# power-sch.net
KiCad netlist of a schematic drawn in Altium Designer
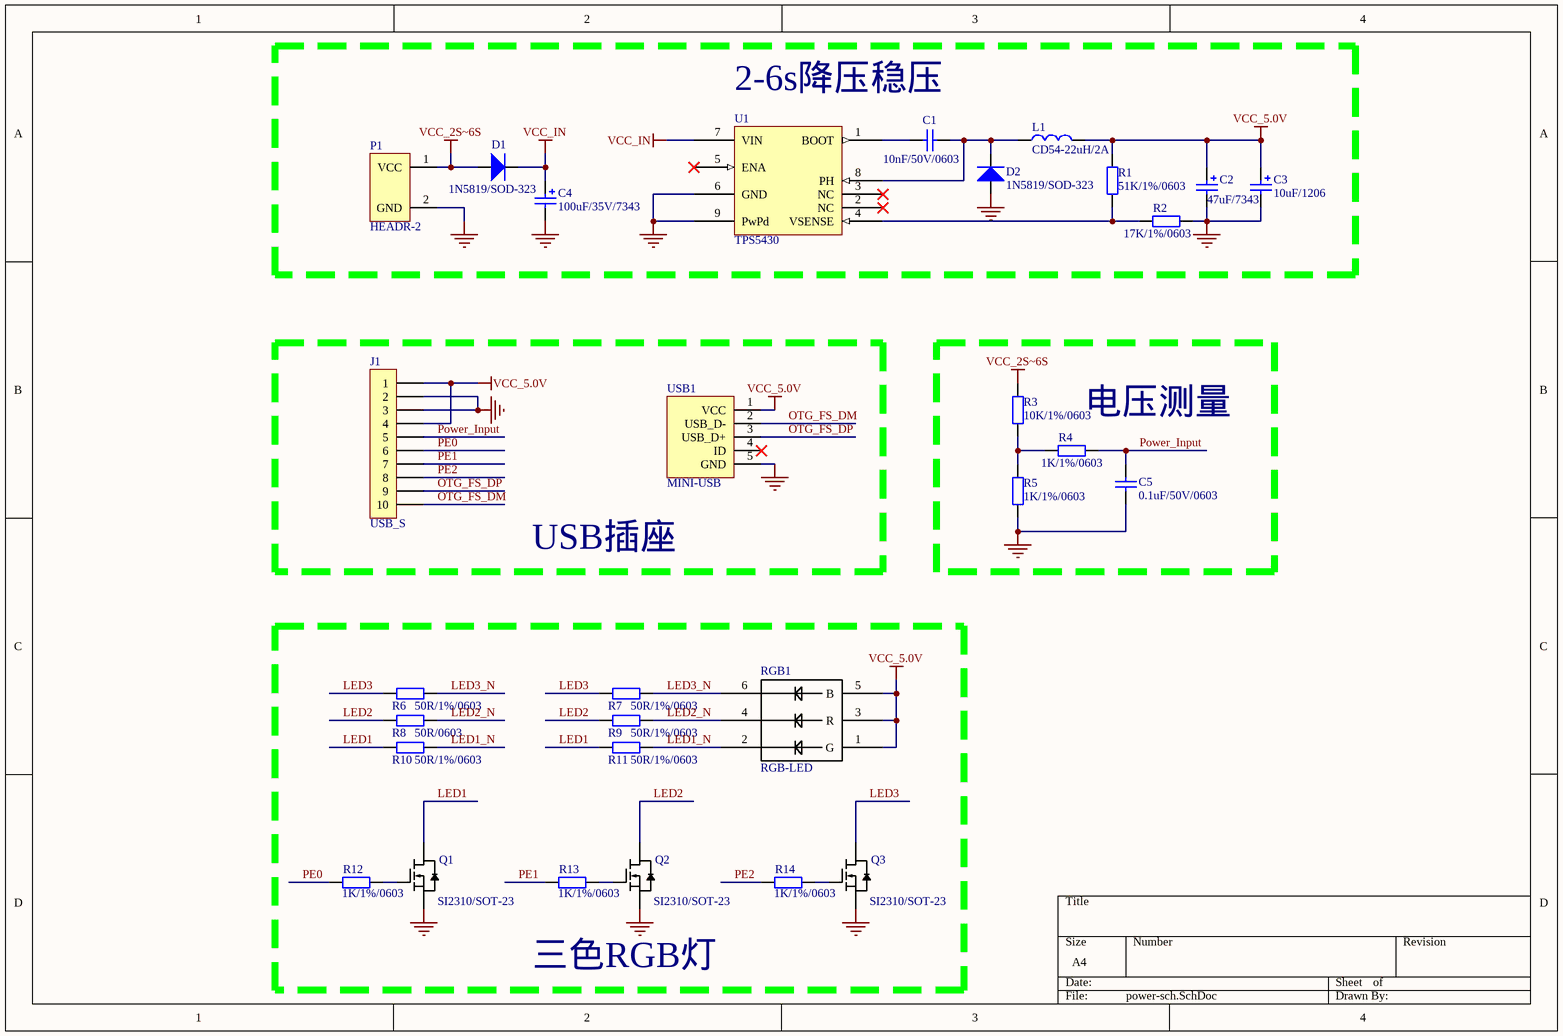
[diagram p0: power-sch.SchDoc]

(export (version "E")
  (design (tool "Eeschema 10.0.6"))
  (components
    (comp (ref "C1")
      (value "10nF/50V/0603")
      (footprint "LC-0603_C")
      (description "Capacitor")
      (fields (field (name "PUBLISHER") "Altium Limited"))
      (libsource (lib "Miscellaneous Devices") (part "Cap"))
    )
    (comp (ref "C2")
      (value "47uF/7343")
      (footprint "LC-CASE-D_7343")
      (description "Polarized Capacitor (Axial)")
      (fields (field (name "PUBLISHER") "Altium Limited"))
      (libsource (lib "Miscellaneous Devices") (part "Cap Pol2"))
    )
    (comp (ref "C3")
      (value "10uF/1206")
      (footprint "LC-CASE-A_3216")
      (description "Polarized Capacitor (Axial)")
      (fields (field (name "PUBLISHER") "Altium Limited"))
      (libsource (lib "Miscellaneous Devices") (part "Cap Pol2"))
    )
    (comp (ref "C4")
      (value "100uF/35V/7343")
      (footprint "LC-CASE-D_7343")
      (description "Polarized Capacitor (Axial)")
      (fields (field (name "PUBLISHER") "Altium Limited"))
      (libsource (lib "Miscellaneous Devices") (part "Cap Pol2"))
    )
    (comp (ref "C5")
      (value "0.1uF/50V/0603")
      (footprint "LC-0603_C")
      (description "Capacitor")
      (fields (field (name "PUBLISHER") "Altium Limited"))
      (libsource (lib "Miscellaneous Devices") (part "Cap"))
    )
    (comp (ref "D1")
      (value "1N5819/SOD-323")
      (footprint "SOD_323_F")
      (libsource (lib "power-schlib") (part "1N5819"))
    )
    (comp (ref "D2")
      (value "1N5819/SOD-323")
      (footprint "SOD_323_F")
      (libsource (lib "power-schlib") (part "1N5819"))
    )
    (comp (ref "J1") (value "USB_S") (footprint "SH 1.0-10P") (libsource (lib "power-schlib") (part "USB_S")))
    (comp (ref "L1")
      (value "CD54-22uH/2A")
      (footprint "L_SMD_10040")
      (libsource (lib "power-schlib") (part "CD54-22uH/2A"))
    )
    (comp (ref "P1")
      (value "HEADR-2")
      (footprint "SH 1.0-2P")
      (libsource (lib "power-schlib") (part "HEADER-PWR"))
    )
    (comp (ref "Q1")
      (value "SI2310/SOT-23")
      (footprint "LC-SOT-23(SOT-23-3)")
      (libsource (lib "altium-import") (part "root_0_SI2310_"))
    )
    (comp (ref "Q2")
      (value "SI2310/SOT-23")
      (footprint "LC-SOT-23(SOT-23-3)")
      (libsource (lib "altium-import") (part "root_0_SI2310_"))
    )
    (comp (ref "Q3")
      (value "SI2310/SOT-23")
      (footprint "LC-SOT-23(SOT-23-3)")
      (libsource (lib "altium-import") (part "root_0_SI2310_"))
    )
    (comp (ref "R1")
      (value "51K/1%/0603")
      (footprint "LC-0603_R")
      (description "Resistor")
      (fields (field (name "PUBLISHER") "Altium Limited"))
      (libsource (lib "") (part "Res2_1"))
    )
    (comp (ref "R2")
      (value "17K/1%/0603")
      (footprint "LC-0603_R")
      (description "Resistor")
      (fields (field (name "PUBLISHER") "Altium Limited"))
      (libsource (lib "") (part "Res2_2"))
    )
    (comp (ref "R3")
      (value "10K/1%/0603")
      (footprint "LC-0603_R")
      (description "Resistor")
      (fields (field (name "PUBLISHER") "Altium Limited"))
      (libsource (lib "") (part "Res2_1"))
    )
    (comp (ref "R4")
      (value "1K/1%/0603")
      (footprint "LC-0603_R")
      (description "Resistor")
      (fields (field (name "PUBLISHER") "Altium Limited"))
      (libsource (lib "") (part "Res2_2"))
    )
    (comp (ref "R5")
      (value "1K/1%/0603")
      (footprint "LC-0603_R")
      (description "Resistor")
      (fields (field (name "PUBLISHER") "Altium Limited"))
      (libsource (lib "") (part "Res2_1"))
    )
    (comp (ref "R6")
      (value "50R/1%/0603")
      (footprint "LC-0603_R")
      (description "Resistor")
      (fields (field (name "PUBLISHER") "Altium Limited"))
      (libsource (lib "Miscellaneous Devices") (part "Res2"))
    )
    (comp (ref "R7")
      (value "50R/1%/0603")
      (footprint "LC-0603_R")
      (description "Resistor")
      (fields (field (name "PUBLISHER") "Altium Limited"))
      (libsource (lib "Miscellaneous Devices") (part "Res2"))
    )
    (comp (ref "R8")
      (value "50R/0603")
      (footprint "LC-0603_R")
      (description "Resistor")
      (fields (field (name "PUBLISHER") "Altium Limited"))
      (libsource (lib "Miscellaneous Devices") (part "Res2"))
    )
    (comp (ref "R9")
      (value "50R/1%/0603")
      (footprint "LC-0603_R")
      (description "Resistor")
      (fields (field (name "PUBLISHER") "Altium Limited"))
      (libsource (lib "Miscellaneous Devices") (part "Res2"))
    )
    (comp (ref "R10")
      (value "50R/1%/0603")
      (footprint "LC-0603_R")
      (description "Resistor")
      (fields (field (name "PUBLISHER") "Altium Limited"))
      (libsource (lib "Miscellaneous Devices") (part "Res2"))
    )
    (comp (ref "R11")
      (value "50R/1%/0603")
      (footprint "LC-0603_R")
      (description "Resistor")
      (fields (field (name "PUBLISHER") "Altium Limited"))
      (libsource (lib "Miscellaneous Devices") (part "Res2"))
    )
    (comp (ref "R12")
      (value "1K/1%/0603")
      (footprint "LC-0603_R")
      (description "Resistor")
      (fields (field (name "PUBLISHER") "Altium Limited"))
      (libsource (lib "Miscellaneous Devices") (part "Res2"))
    )
    (comp (ref "R13")
      (value "1K/1%/0603")
      (footprint "LC-0603_R")
      (description "Resistor")
      (fields (field (name "PUBLISHER") "Altium Limited"))
      (libsource (lib "Miscellaneous Devices") (part "Res2"))
    )
    (comp (ref "R14")
      (value "1K/1%/0603")
      (footprint "LC-0603_R")
      (description "Resistor")
      (fields (field (name "PUBLISHER") "Altium Limited"))
      (libsource (lib "Miscellaneous Devices") (part "Res2"))
    )
    (comp (ref "RGB1")
      (value "RGB-LED")
      (footprint "RGB-5050")
      (libsource (lib "power-schlib") (part "RGB-5050"))
    )
    (comp (ref "U1")
      (value "TPS5430")
      (footprint "SOIC_8_PAD")
      (libsource (lib "power-schlib") (part "TPS5430"))
    )
    (comp (ref "USB1")
      (value "MINI-USB")
      (footprint "mini_usb_AB")
      (libsource (lib "power-schlib") (part "MINI-USB"))
    )
  )
  (nets
    (net (code "1") (name "/LED1") (class "Default")
      (node (ref "Q1") (pin "3") (pinfunction "DRAIN_3") (pintype "passive"))
      (node (ref "R10") (pin "1") (pinfunction "1_1") (pintype "passive"))
      (node (ref "R11") (pin "1") (pinfunction "1_1") (pintype "passive"))
    )
    (net (code "2") (name "/LED1_N") (class "Default")
      (node (ref "R10") (pin "2") (pinfunction "2_2") (pintype "passive"))
      (node (ref "R11") (pin "2") (pinfunction "2_2") (pintype "passive"))
      (node (ref "RGB1") (pin "2") (pinfunction "2_2") (pintype "passive"))
    )
    (net (code "3") (name "/LED2") (class "Default")
      (node (ref "Q2") (pin "3") (pinfunction "DRAIN_3") (pintype "passive"))
      (node (ref "R8") (pin "1") (pinfunction "1_1") (pintype "passive"))
      (node (ref "R9") (pin "1") (pinfunction "1_1") (pintype "passive"))
    )
    (net (code "4") (name "/LED2_N") (class "Default")
      (node (ref "R8") (pin "2") (pinfunction "2_2") (pintype "passive"))
      (node (ref "R9") (pin "2") (pinfunction "2_2") (pintype "passive"))
      (node (ref "RGB1") (pin "4") (pinfunction "4_4") (pintype "passive"))
    )
    (net (code "5") (name "/LED3") (class "Default")
      (node (ref "Q3") (pin "3") (pinfunction "DRAIN_3") (pintype "passive"))
      (node (ref "R6") (pin "1") (pinfunction "1_1") (pintype "passive"))
      (node (ref "R7") (pin "1") (pinfunction "1_1") (pintype "passive"))
    )
    (net (code "6") (name "/LED3_N") (class "Default")
      (node (ref "R6") (pin "2") (pinfunction "2_2") (pintype "passive"))
      (node (ref "R7") (pin "2") (pinfunction "2_2") (pintype "passive"))
      (node (ref "RGB1") (pin "6") (pinfunction "6_6") (pintype "passive"))
    )
    (net (code "7") (name "/OTG_FS_DM") (class "Default")
      (node (ref "J1") (pin "10") (pinfunction "10_10") (pintype "passive"))
      (node (ref "USB1") (pin "2") (pinfunction "USB_D-_2") (pintype "passive"))
    )
    (net (code "8") (name "/OTG_FS_DP") (class "Default")
      (node (ref "J1") (pin "9") (pinfunction "9_9") (pintype "passive"))
      (node (ref "USB1") (pin "3") (pinfunction "USB_D+_3") (pintype "passive"))
    )
    (net (code "9") (name "/PE0") (class "Default")
      (node (ref "J1") (pin "6") (pinfunction "6_6") (pintype "passive"))
      (node (ref "R12") (pin "1") (pinfunction "1_1") (pintype "passive"))
    )
    (net (code "10") (name "/PE1") (class "Default")
      (node (ref "J1") (pin "7") (pinfunction "7_7") (pintype "passive"))
      (node (ref "R13") (pin "1") (pinfunction "1_1") (pintype "passive"))
    )
    (net (code "11") (name "/PE2") (class "Default")
      (node (ref "J1") (pin "8") (pinfunction "8_8") (pintype "passive"))
      (node (ref "R14") (pin "1") (pinfunction "1_1") (pintype "passive"))
    )
    (net (code "12") (name "/Power_Input") (class "Default")
      (node (ref "C5") (pin "2") (pinfunction "2_2") (pintype "passive"))
      (node (ref "J1") (pin "5") (pinfunction "5_5") (pintype "passive"))
      (node (ref "R4") (pin "1") (pinfunction "1_1") (pintype "passive"))
    )
    (net (code "13") (name "GND") (class "Default")
      (node (ref "C2") (pin "2") (pinfunction "2_2") (pintype "passive"))
      (node (ref "C3") (pin "2") (pinfunction "2_2") (pintype "passive"))
      (node (ref "C4") (pin "2") (pinfunction "2_2") (pintype "passive"))
      (node (ref "C5") (pin "1") (pinfunction "1_1") (pintype "passive"))
      (node (ref "D2") (pin "1") (pinfunction "1_1") (pintype "passive"))
      (node (ref "J1") (pin "2") (pinfunction "2_2") (pintype "passive"))
      (node (ref "J1") (pin "3") (pinfunction "3_3") (pintype "passive"))
      (node (ref "P1") (pin "2") (pinfunction "GND_2") (pintype "power_in"))
      (node (ref "Q1") (pin "2") (pinfunction "SOURCE_2") (pintype "passive"))
      (node (ref "Q2") (pin "2") (pinfunction "SOURCE_2") (pintype "passive"))
      (node (ref "Q3") (pin "2") (pinfunction "SOURCE_2") (pintype "passive"))
      (node (ref "R2") (pin "1") (pinfunction "1_1") (pintype "passive"))
      (node (ref "R5") (pin "1") (pinfunction "1_1") (pintype "passive"))
      (node (ref "U1") (pin "6") (pinfunction "GND_6") (pintype "power_in"))
      (node (ref "U1") (pin "9") (pinfunction "PwPd_9") (pintype "power_in"))
      (node (ref "USB1") (pin "5") (pinfunction "GND_5") (pintype "power_in"))
    )
    (net (code "14") (name "Net-(Q1-GATE)") (class "Default")
      (node (ref "Q1") (pin "1") (pinfunction "GATE_1") (pintype "passive"))
      (node (ref "R12") (pin "2") (pinfunction "2_2") (pintype "passive"))
    )
    (net (code "15") (name "Net-(Q2-GATE)") (class "Default")
      (node (ref "Q2") (pin "1") (pinfunction "GATE_1") (pintype "passive"))
      (node (ref "R13") (pin "2") (pinfunction "2_2") (pintype "passive"))
    )
    (net (code "16") (name "Net-(Q3-GATE)") (class "Default")
      (node (ref "Q3") (pin "1") (pinfunction "GATE_1") (pintype "passive"))
      (node (ref "R14") (pin "2") (pinfunction "2_2") (pintype "passive"))
    )
    (net (code "17") (name "Net-(R3-Pad1)") (class "Default")
      (node (ref "R3") (pin "1") (pinfunction "1_1") (pintype "passive"))
      (node (ref "R4") (pin "2") (pinfunction "2_2") (pintype "passive"))
      (node (ref "R5") (pin "2") (pinfunction "2_2") (pintype "passive"))
    )
    (net (code "18") (name "Net-(U1-BOOT)") (class "Default")
      (node (ref "C1") (pin "1") (pinfunction "1_1") (pintype "passive"))
      (node (ref "U1") (pin "1") (pinfunction "BOOT_1") (pintype "output"))
    )
    (net (code "19") (name "Net-(U1-PH)") (class "Default")
      (node (ref "C1") (pin "2") (pinfunction "2_2") (pintype "passive"))
      (node (ref "D2") (pin "2") (pinfunction "2_2") (pintype "passive"))
      (node (ref "L1") (pin "1") (pinfunction "1_1") (pintype "passive"))
      (node (ref "U1") (pin "8") (pinfunction "PH_8") (pintype "input"))
    )
    (net (code "20") (name "Net-(U1-VSENSE)") (class "Default")
      (node (ref "R1") (pin "1") (pinfunction "1_1") (pintype "passive"))
      (node (ref "R2") (pin "2") (pinfunction "2_2") (pintype "passive"))
      (node (ref "U1") (pin "4") (pinfunction "VSENSE_4") (pintype "input"))
    )
    (net (code "21") (name "VCC_2S~6S") (class "Default")
      (node (ref "D1") (pin "1") (pinfunction "1_1") (pintype "passive"))
      (node (ref "P1") (pin "1") (pinfunction "VCC_1") (pintype "power_in"))
      (node (ref "R3") (pin "2") (pinfunction "2_2") (pintype "passive"))
    )
    (net (code "22") (name "VCC_5.0V") (class "Default")
      (node (ref "C2") (pin "1") (pinfunction "1_1") (pintype "passive"))
      (node (ref "C3") (pin "1") (pinfunction "1_1") (pintype "passive"))
      (node (ref "J1") (pin "1") (pinfunction "1_1") (pintype "passive"))
      (node (ref "J1") (pin "4") (pinfunction "4_4") (pintype "passive"))
      (node (ref "L1") (pin "2") (pinfunction "2_2") (pintype "passive"))
      (node (ref "R1") (pin "2") (pinfunction "2_2") (pintype "passive"))
      (node (ref "RGB1") (pin "1") (pinfunction "G_1") (pintype "passive"))
      (node (ref "RGB1") (pin "3") (pinfunction "R_3") (pintype "passive"))
      (node (ref "RGB1") (pin "5") (pinfunction "B_5") (pintype "passive"))
      (node (ref "USB1") (pin "1") (pinfunction "VCC_1") (pintype "power_in"))
    )
    (net (code "23") (name "VCC_IN") (class "Default")
      (node (ref "C4") (pin "1") (pinfunction "1_1") (pintype "passive"))
      (node (ref "D1") (pin "2") (pinfunction "2_2") (pintype "passive"))
      (node (ref "U1") (pin "7") (pinfunction "VIN_7") (pintype "power_in"))
    )
    (net (code "24") (name "unconnected-(U1-ENA-Pad5)") (class "Default")
      (node (ref "U1") (pin "5") (pinfunction "ENA_5") (pintype "input+no_connect"))
    )
    (net (code "25") (name "unconnected-(U1-NC-Pad2)") (class "Default")
      (node (ref "U1") (pin "2") (pinfunction "NC_2") (pintype "passive+no_connect"))
    )
    (net (code "26") (name "unconnected-(U1-NC-Pad3)") (class "Default")
      (node (ref "U1") (pin "3") (pinfunction "NC_3") (pintype "passive+no_connect"))
    )
    (net (code "27") (name "unconnected-(USB1-ID-Pad4)") (class "Default")
      (node (ref "USB1") (pin "4") (pinfunction "ID_4") (pintype "passive+no_connect"))
    )
  )
)
